# zero_board.net
KiCad netlist of a schematic drawn in EAGLE
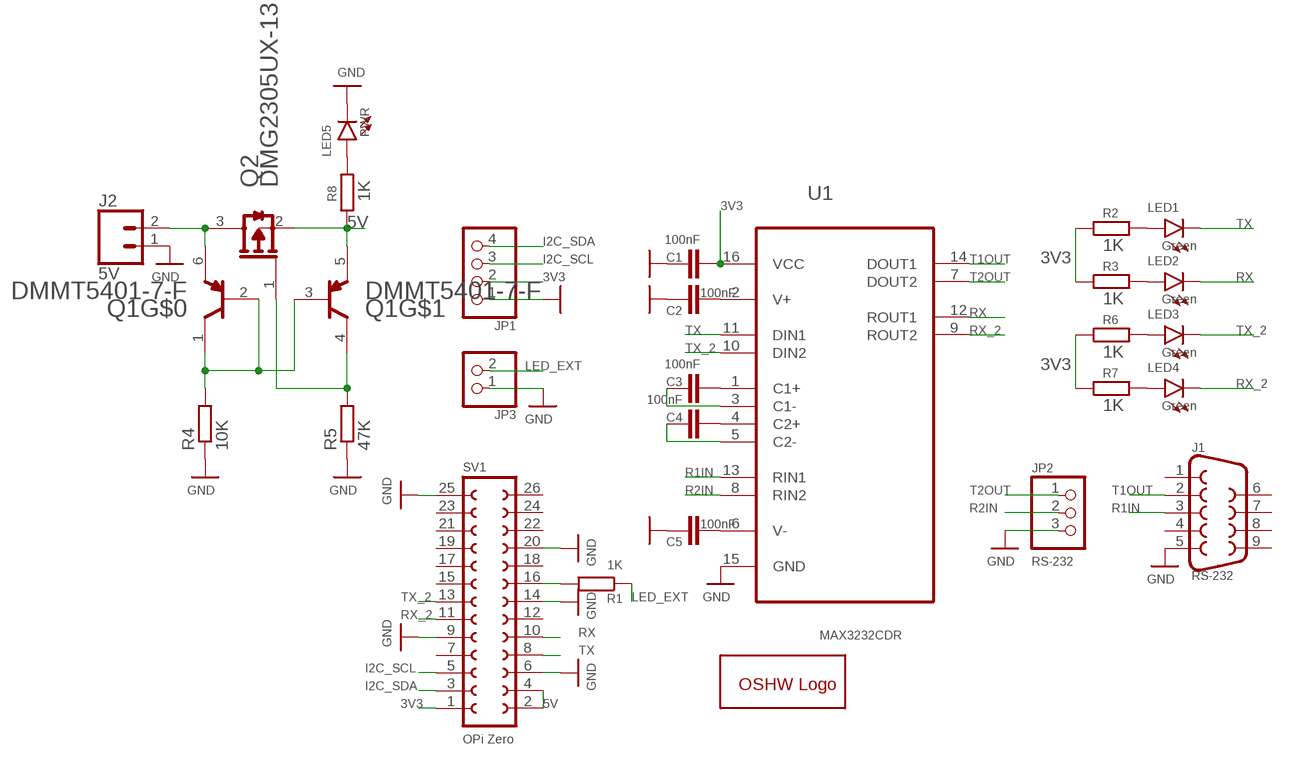
[diagram p0: schematic, sheet 1]

(export (version "E")
  (design (tool "Eeschema 10.0.6"))
  (components
    (comp (ref "C1")
      (value "100nF")
      (footprint "eagle-import:C0603")
      (libsource (lib "eagle-import") (part "C-EUC0603"))
    )
    (comp (ref "C2")
      (value "100nF")
      (footprint "eagle-import:C0603")
      (libsource (lib "eagle-import") (part "C-EUC0603"))
    )
    (comp (ref "C3")
      (value "100nF")
      (footprint "eagle-import:C0603")
      (libsource (lib "eagle-import") (part "C-EUC0603"))
    )
    (comp (ref "C4")
      (value "100nF")
      (footprint "eagle-import:C0603")
      (libsource (lib "eagle-import") (part "C-EUC0603"))
    )
    (comp (ref "C5")
      (value "100nF")
      (footprint "eagle-import:C0603")
      (libsource (lib "eagle-import") (part "C-EUC0603"))
    )
    (comp (ref "GOLD_ORB_SM1")
      (value "OSHWLOGOLOGO5MM")
      (footprint "eagle-import:OSHW_5MM")
      (libsource (lib "eagle-import") (part "OSHWLOGOLOGO5MM"))
    )
    (comp (ref "J1")
      (value "RS-232")
      (footprint "eagle-import:DB9")
      (libsource (lib "eagle-import") (part "DB9FEMALE"))
    )
    (comp (ref "J2")
      (value "5V")
      (footprint "eagle-import:SCREWTERMINAL-3.5MM-2")
      (libsource (lib "eagle-import") (part "CONN_023.5MM"))
    )
    (comp (ref "JP1")
      (value "OLED")
      (footprint "eagle-import:1X04")
      (libsource (lib "eagle-import") (part "PINHD-1X4"))
    )
    (comp (ref "JP2")
      (value "RS-232")
      (footprint "eagle-import:1X03")
      (libsource (lib "eagle-import") (part "PINHD-1X3"))
    )
    (comp (ref "JP3")
      (value "LED")
      (footprint "eagle-import:1X02")
      (libsource (lib "eagle-import") (part "PINHD-1X2"))
    )
    (comp (ref "LED1")
      (value "Green")
      (footprint "eagle-import:CHIP-LED0603")
      (libsource (lib "eagle-import") (part "LEDCHIP-LED0603"))
    )
    (comp (ref "LED2")
      (value "Green")
      (footprint "eagle-import:CHIP-LED0603")
      (libsource (lib "eagle-import") (part "LEDCHIP-LED0603"))
    )
    (comp (ref "LED3")
      (value "Green")
      (footprint "eagle-import:CHIP-LED0603")
      (libsource (lib "eagle-import") (part "LEDCHIP-LED0603"))
    )
    (comp (ref "LED4")
      (value "Green")
      (footprint "eagle-import:CHIP-LED0603")
      (libsource (lib "eagle-import") (part "LEDCHIP-LED0603"))
    )
    (comp (ref "LED5")
      (value "PWR")
      (footprint "eagle-import:CHIP-LED0603")
      (libsource (lib "eagle-import") (part "LEDCHIP-LED0603"))
    )
    (comp (ref "Q1")
      (value "DIODES_DMMT5401-7-FDIODES_DMMT5401-7-F_0_0")
      (footprint "eagle-import:DIODES_DMMT5401-7-F_0")
      (fields
        (field (name "DIGIKEY_PART_NUMBER") "DMMT5401-FDICT-ND")
        (field (name "MF") "Diodes")
        (field (name "MOUSER_PART_NUMBER") "621-DMMT5401-7-F")
      )
      (libsource (lib "eagle-import") (part "DIODES_DMMT5401-7-FDIODES_DMMT5401-7-F_0_0"))
    )
    (comp (ref "Q2")
      (value "DIODES_INC._DMG2305UX-13DIODES_INC._DMG2305UX-13_0_0")
      (footprint "eagle-import:DIODES_INC._DMG2305UX-13_0")
      (fields
        (field (name "DIGIKEY_PART_NUMBER") "DMG2305UX-13DICT-ND")
        (field (name "MF") "Diodes Inc.")
        (field (name "MOUSER_PART_NUMBER") "621-DMG2305UX-13")
      )
      (libsource (lib "eagle-import") (part "DIODES_INC._DMG2305UX-13DIODES_INC._DMG2305UX-13_0_0"))
    )
    (comp (ref "R1")
      (value "1K")
      (footprint "eagle-import:R0603")
      (libsource (lib "eagle-import") (part "R-EU_R0603"))
    )
    (comp (ref "R2")
      (value "1K")
      (footprint "eagle-import:R0603")
      (libsource (lib "eagle-import") (part "resistor_348_R-EU_R0603"))
    )
    (comp (ref "R3")
      (value "1K")
      (footprint "eagle-import:R0603")
      (libsource (lib "eagle-import") (part "resistor_348_R-EU_R0603"))
    )
    (comp (ref "R4")
      (value "10K")
      (footprint "eagle-import:R0402")
      (libsource (lib "eagle-import") (part "rcl_334_R-EU_R0402"))
    )
    (comp (ref "R5")
      (value "47K")
      (footprint "eagle-import:R0402")
      (libsource (lib "eagle-import") (part "rcl_334_R-EU_R0402"))
    )
    (comp (ref "R6")
      (value "1K")
      (footprint "eagle-import:R0603")
      (libsource (lib "eagle-import") (part "resistor_348_R-EU_R0603"))
    )
    (comp (ref "R7")
      (value "1K")
      (footprint "eagle-import:R0603")
      (libsource (lib "eagle-import") (part "resistor_348_R-EU_R0603"))
    )
    (comp (ref "R8")
      (value "1K")
      (footprint "eagle-import:R0603")
      (libsource (lib "eagle-import") (part "resistor_348_R-EU_R0603"))
    )
    (comp (ref "SV1")
      (value "OPi Zero")
      (footprint "eagle-import:FE13-2")
      (libsource (lib "eagle-import") (part "FE13-2"))
    )
    (comp (ref "U1")
      (value "MAX3232CDR")
      (footprint "eagle-import:SOIC127P600X175-16N")
      (libsource (lib "eagle-import") (part "MAX3232CDR"))
    )
  )
  (nets
    (net (code "1") (name "/3V3") (class "Default")
      (node (ref "C1") (pin "2") (pinfunction "2_2") (pintype "passive"))
      (node (ref "JP1") (pin "2") (pinfunction "2_2") (pintype "passive"))
      (node (ref "R2") (pin "1") (pinfunction "1_1") (pintype "passive"))
      (node (ref "R3") (pin "1") (pinfunction "1_1") (pintype "passive"))
      (node (ref "R6") (pin "1") (pinfunction "1_1") (pintype "passive"))
      (node (ref "R7") (pin "1") (pinfunction "1_1") (pintype "passive"))
      (node (ref "SV1") (pin "1") (pinfunction "1_1") (pintype "passive"))
      (node (ref "U1") (pin "16") (pinfunction "VCC_16") (pintype "power_in"))
    )
    (net (code "2") (name "/5V") (class "Default")
      (node (ref "Q1") (pin "5") (pinfunction "E2_5") (pintype "passive"))
      (node (ref "Q2") (pin "2") (pinfunction "S_2") (pintype "passive"))
      (node (ref "R8") (pin "1") (pinfunction "1_1") (pintype "passive"))
      (node (ref "SV1") (pin "2") (pinfunction "2_2") (pintype "passive"))
      (node (ref "SV1") (pin "4") (pinfunction "4_4") (pintype "passive"))
    )
    (net (code "3") (name "/I2C_SCL") (class "Default")
      (node (ref "JP1") (pin "3") (pinfunction "3_3") (pintype "passive"))
      (node (ref "SV1") (pin "5") (pinfunction "5_5") (pintype "passive"))
    )
    (net (code "4") (name "/I2C_SDA") (class "Default")
      (node (ref "JP1") (pin "4") (pinfunction "4_4") (pintype "passive"))
      (node (ref "SV1") (pin "3") (pinfunction "3_3") (pintype "passive"))
    )
    (net (code "5") (name "/LED_EXT") (class "Default")
      (node (ref "JP3") (pin "2") (pinfunction "2_2") (pintype "passive"))
      (node (ref "R1") (pin "1") (pinfunction "1_1") (pintype "passive"))
    )
    (net (code "6") (name "/R1IN") (class "Default")
      (node (ref "J1") (pin "3") (pinfunction "3_3") (pintype "passive"))
      (node (ref "U1") (pin "13") (pinfunction "RIN1_13") (pintype "input"))
    )
    (net (code "7") (name "/R2IN") (class "Default")
      (node (ref "JP2") (pin "2") (pinfunction "2_2") (pintype "passive"))
      (node (ref "U1") (pin "8") (pinfunction "RIN2_8") (pintype "input"))
    )
    (net (code "8") (name "/RX") (class "Default")
      (node (ref "LED2") (pin "C") (pinfunction "C_C") (pintype "passive"))
      (node (ref "SV1") (pin "10") (pinfunction "10_10") (pintype "passive"))
      (node (ref "U1") (pin "12") (pinfunction "ROUT1_12") (pintype "output"))
    )
    (net (code "9") (name "/RX_2") (class "Default")
      (node (ref "LED4") (pin "C") (pinfunction "C_C") (pintype "passive"))
      (node (ref "SV1") (pin "11") (pinfunction "11_11") (pintype "passive"))
      (node (ref "U1") (pin "9") (pinfunction "ROUT2_9") (pintype "output"))
    )
    (net (code "10") (name "/T1OUT") (class "Default")
      (node (ref "J1") (pin "2") (pinfunction "2_2") (pintype "passive"))
      (node (ref "U1") (pin "14") (pinfunction "DOUT1_14") (pintype "output"))
    )
    (net (code "11") (name "/T2OUT") (class "Default")
      (node (ref "JP2") (pin "1") (pinfunction "1_1") (pintype "passive"))
      (node (ref "U1") (pin "7") (pinfunction "DOUT2_7") (pintype "output"))
    )
    (net (code "12") (name "/TX") (class "Default")
      (node (ref "LED1") (pin "C") (pinfunction "C_C") (pintype "passive"))
      (node (ref "SV1") (pin "8") (pinfunction "8_8") (pintype "passive"))
      (node (ref "U1") (pin "11") (pinfunction "DIN1_11") (pintype "input"))
    )
    (net (code "13") (name "/TX_2") (class "Default")
      (node (ref "LED3") (pin "C") (pinfunction "C_C") (pintype "passive"))
      (node (ref "SV1") (pin "13") (pinfunction "13_13") (pintype "passive"))
      (node (ref "U1") (pin "10") (pinfunction "DIN2_10") (pintype "input"))
    )
    (net (code "14") (name "GND") (class "Default")
      (node (ref "C1") (pin "1") (pinfunction "1_1") (pintype "passive"))
      (node (ref "C2") (pin "1") (pinfunction "1_1") (pintype "passive"))
      (node (ref "C5") (pin "1") (pinfunction "1_1") (pintype "passive"))
      (node (ref "J1") (pin "5") (pinfunction "5_5") (pintype "passive"))
      (node (ref "J2") (pin "1") (pinfunction "1_1") (pintype "passive"))
      (node (ref "JP1") (pin "1") (pinfunction "1_1") (pintype "passive"))
      (node (ref "JP2") (pin "3") (pinfunction "3_3") (pintype "passive"))
      (node (ref "JP3") (pin "1") (pinfunction "1_1") (pintype "passive"))
      (node (ref "LED5") (pin "C") (pinfunction "C_C") (pintype "passive"))
      (node (ref "R4") (pin "1") (pinfunction "1_1") (pintype "passive"))
      (node (ref "R5") (pin "1") (pinfunction "1_1") (pintype "passive"))
      (node (ref "SV1") (pin "14") (pinfunction "14_14") (pintype "passive"))
      (node (ref "SV1") (pin "20") (pinfunction "20_20") (pintype "passive"))
      (node (ref "SV1") (pin "25") (pinfunction "25_25") (pintype "passive"))
      (node (ref "SV1") (pin "6") (pinfunction "6_6") (pintype "passive"))
      (node (ref "SV1") (pin "9") (pinfunction "9_9") (pintype "passive"))
      (node (ref "U1") (pin "15") (pinfunction "GND_15") (pintype "passive"))
    )
    (net (code "15") (name "Net-(LED1-PadA)") (class "Default")
      (node (ref "LED1") (pin "A") (pinfunction "A_A") (pintype "passive"))
      (node (ref "R2") (pin "2") (pinfunction "2_2") (pintype "passive"))
    )
    (net (code "16") (name "Net-(LED2-PadA)") (class "Default")
      (node (ref "LED2") (pin "A") (pinfunction "A_A") (pintype "passive"))
      (node (ref "R3") (pin "2") (pinfunction "2_2") (pintype "passive"))
    )
    (net (code "17") (name "Net-(LED3-PadA)") (class "Default")
      (node (ref "LED3") (pin "A") (pinfunction "A_A") (pintype "passive"))
      (node (ref "R6") (pin "2") (pinfunction "2_2") (pintype "passive"))
    )
    (net (code "18") (name "Net-(LED4-PadA)") (class "Default")
      (node (ref "LED4") (pin "A") (pinfunction "A_A") (pintype "passive"))
      (node (ref "R7") (pin "2") (pinfunction "2_2") (pintype "passive"))
    )
    (net (code "19") (name "Net-(LED5-PadA)") (class "Default")
      (node (ref "LED5") (pin "A") (pinfunction "A_A") (pintype "passive"))
      (node (ref "R8") (pin "2") (pinfunction "2_2") (pintype "passive"))
    )
    (net (code "20") (name "Net-(Q1A-B1)") (class "Default")
      (node (ref "Q1") (pin "1") (pinfunction "C1_1") (pintype "passive"))
      (node (ref "Q1") (pin "2") (pinfunction "B1_2") (pintype "passive"))
      (node (ref "Q1") (pin "3") (pinfunction "B2_3") (pintype "passive"))
      (node (ref "R4") (pin "2") (pinfunction "2_2") (pintype "passive"))
    )
    (net (code "21") (name "Net-(Q1A-E1)") (class "Default")
      (node (ref "J2") (pin "2") (pinfunction "2_2") (pintype "passive"))
      (node (ref "Q1") (pin "6") (pinfunction "E1_6") (pintype "passive"))
      (node (ref "Q2") (pin "3") (pinfunction "D_3") (pintype "passive"))
    )
    (net (code "22") (name "Net-(Q1B-C2)") (class "Default")
      (node (ref "Q1") (pin "4") (pinfunction "C2_4") (pintype "passive"))
      (node (ref "Q2") (pin "1") (pinfunction "G_1") (pintype "passive"))
      (node (ref "R5") (pin "2") (pinfunction "2_2") (pintype "passive"))
    )
    (net (code "23") (name "Net-(R1-Pad2)") (class "Default")
      (node (ref "R1") (pin "2") (pinfunction "2_2") (pintype "passive"))
      (node (ref "SV1") (pin "16") (pinfunction "16_16") (pintype "passive"))
    )
    (net (code "24") (name "Net-(U1-C1+)") (class "Default")
      (node (ref "C3") (pin "2") (pinfunction "2_2") (pintype "passive"))
      (node (ref "U1") (pin "1") (pinfunction "C1+_1") (pintype "input"))
    )
    (net (code "25") (name "Net-(U1-C1-)") (class "Default")
      (node (ref "C3") (pin "1") (pinfunction "1_1") (pintype "passive"))
      (node (ref "U1") (pin "3") (pinfunction "C1-_3") (pintype "input"))
    )
    (net (code "26") (name "Net-(U1-C2+)") (class "Default")
      (node (ref "C4") (pin "2") (pinfunction "2_2") (pintype "passive"))
      (node (ref "U1") (pin "4") (pinfunction "C2+_4") (pintype "input"))
    )
    (net (code "27") (name "Net-(U1-C2-)") (class "Default")
      (node (ref "C4") (pin "1") (pinfunction "1_1") (pintype "passive"))
      (node (ref "U1") (pin "5") (pinfunction "C2-_5") (pintype "input"))
    )
    (net (code "28") (name "Net-(U1-V+)") (class "Default")
      (node (ref "C2") (pin "2") (pinfunction "2_2") (pintype "passive"))
      (node (ref "U1") (pin "2") (pinfunction "V+_2") (pintype "input"))
    )
    (net (code "29") (name "Net-(U1-V-)") (class "Default")
      (node (ref "C5") (pin "2") (pinfunction "2_2") (pintype "passive"))
      (node (ref "U1") (pin "6") (pinfunction "V-_6") (pintype "input"))
    )
    (net (code "30") (name "unconnected-(J1-Pad1)") (class "Default")
      (node (ref "J1") (pin "1") (pinfunction "1_1") (pintype "passive"))
    )
    (net (code "31") (name "unconnected-(J1-Pad4)") (class "Default")
      (node (ref "J1") (pin "4") (pinfunction "4_4") (pintype "passive"))
    )
    (net (code "32") (name "unconnected-(J1-Pad6)") (class "Default")
      (node (ref "J1") (pin "6") (pinfunction "6_6") (pintype "passive"))
    )
    (net (code "33") (name "unconnected-(J1-Pad7)") (class "Default")
      (node (ref "J1") (pin "7") (pinfunction "7_7") (pintype "passive"))
    )
    (net (code "34") (name "unconnected-(J1-Pad8)") (class "Default")
      (node (ref "J1") (pin "8") (pinfunction "8_8") (pintype "passive"))
    )
    (net (code "35") (name "unconnected-(J1-Pad9)") (class "Default")
      (node (ref "J1") (pin "9") (pinfunction "9_9") (pintype "passive"))
    )
    (net (code "36") (name "unconnected-(SV1-Pad7)") (class "Default")
      (node (ref "SV1") (pin "7") (pinfunction "7_7") (pintype "passive"))
    )
    (net (code "37") (name "unconnected-(SV1-Pad12)") (class "Default")
      (node (ref "SV1") (pin "12") (pinfunction "12_12") (pintype "passive"))
    )
    (net (code "38") (name "unconnected-(SV1-Pad15)") (class "Default")
      (node (ref "SV1") (pin "15") (pinfunction "15_15") (pintype "passive"))
    )
    (net (code "39") (name "unconnected-(SV1-Pad17)") (class "Default")
      (node (ref "SV1") (pin "17") (pinfunction "17_17") (pintype "passive"))
    )
    (net (code "40") (name "unconnected-(SV1-Pad18)") (class "Default")
      (node (ref "SV1") (pin "18") (pinfunction "18_18") (pintype "passive"))
    )
    (net (code "41") (name "unconnected-(SV1-Pad19)") (class "Default")
      (node (ref "SV1") (pin "19") (pinfunction "19_19") (pintype "passive"))
    )
    (net (code "42") (name "unconnected-(SV1-Pad21)") (class "Default")
      (node (ref "SV1") (pin "21") (pinfunction "21_21") (pintype "passive"))
    )
    (net (code "43") (name "unconnected-(SV1-Pad22)") (class "Default")
      (node (ref "SV1") (pin "22") (pinfunction "22_22") (pintype "passive"))
    )
    (net (code "44") (name "unconnected-(SV1-Pad23)") (class "Default")
      (node (ref "SV1") (pin "23") (pinfunction "23_23") (pintype "passive"))
    )
    (net (code "45") (name "unconnected-(SV1-Pad24)") (class "Default")
      (node (ref "SV1") (pin "24") (pinfunction "24_24") (pintype "passive"))
    )
    (net (code "46") (name "unconnected-(SV1-Pad26)") (class "Default")
      (node (ref "SV1") (pin "26") (pinfunction "26_26") (pintype "passive"))
    )
  )
)
